# PF.net
KiCad netlist of a schematic drawn in EAGLE
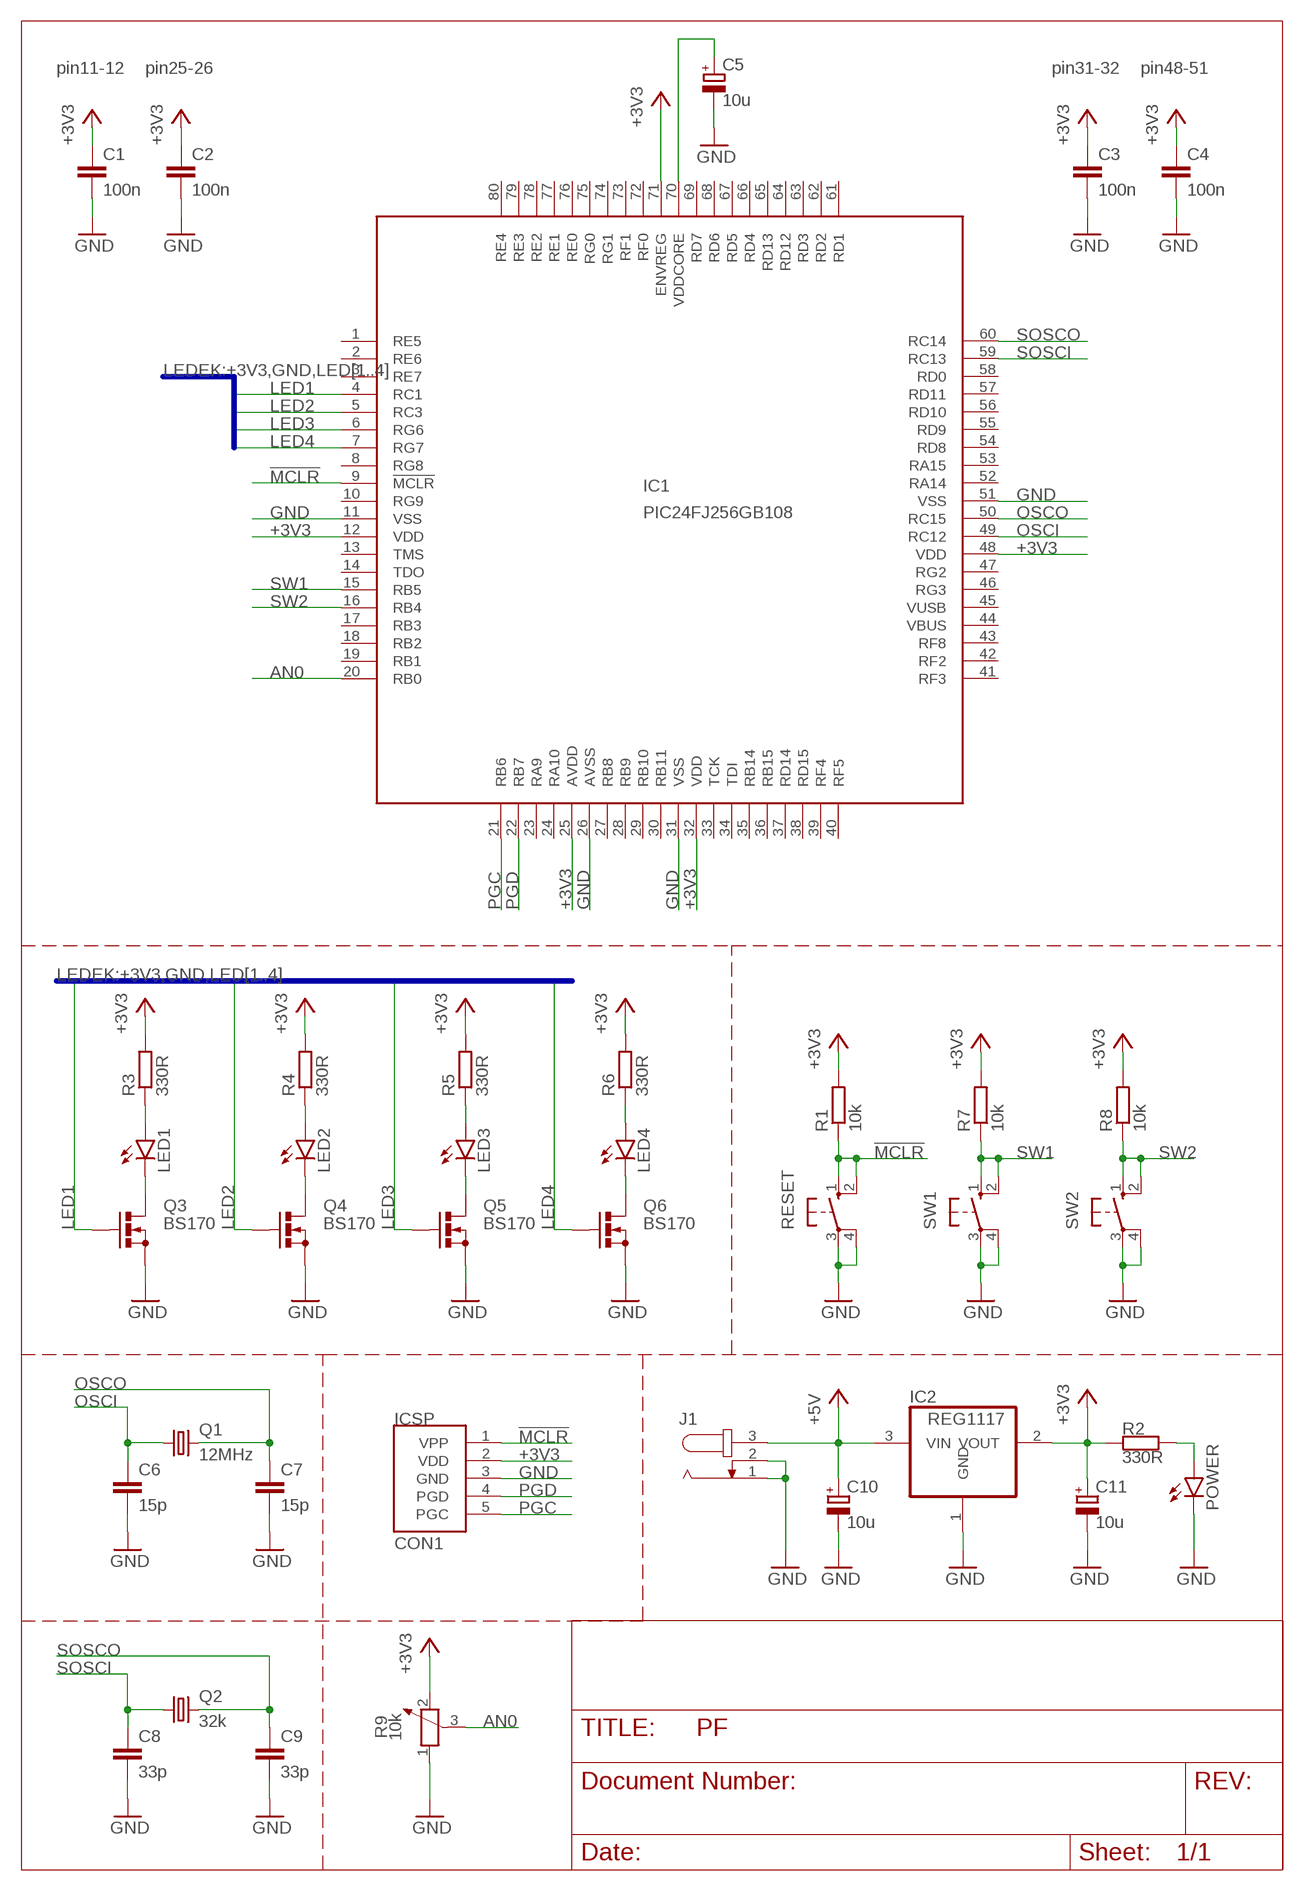
[diagram p0: schematic, sheet 1]

(export (version "E")
  (design (tool "Eeschema 10.0.6"))
  (components
    (comp (ref "C1")
      (value "100n")
      (footprint "eagle-import:C1206")
      (libsource (lib "eagle-import") (part "C-EUC1206"))
    )
    (comp (ref "C2")
      (value "100n")
      (footprint "eagle-import:C1206")
      (libsource (lib "eagle-import") (part "C-EUC1206"))
    )
    (comp (ref "C3")
      (value "100n")
      (footprint "eagle-import:C1206")
      (libsource (lib "eagle-import") (part "C-EUC1206"))
    )
    (comp (ref "C4")
      (value "100n")
      (footprint "eagle-import:C1206")
      (libsource (lib "eagle-import") (part "C-EUC1206"))
    )
    (comp (ref "C5")
      (value "10u")
      (footprint "eagle-import:SMC_D")
      (libsource (lib "eagle-import") (part "CPOL-EUSMCD"))
    )
    (comp (ref "C6")
      (value "15p")
      (footprint "eagle-import:C1206")
      (libsource (lib "eagle-import") (part "C-EUC1206"))
    )
    (comp (ref "C7")
      (value "15p")
      (footprint "eagle-import:C1206")
      (libsource (lib "eagle-import") (part "C-EUC1206"))
    )
    (comp (ref "C8")
      (value "33p")
      (footprint "eagle-import:C1206")
      (libsource (lib "eagle-import") (part "C-EUC1206"))
    )
    (comp (ref "C9")
      (value "33p")
      (footprint "eagle-import:C1206")
      (libsource (lib "eagle-import") (part "C-EUC1206"))
    )
    (comp (ref "C10")
      (value "10u")
      (footprint "eagle-import:SMC_D")
      (libsource (lib "eagle-import") (part "CPOL-EUSMCD"))
    )
    (comp (ref "C11")
      (value "10u")
      (footprint "eagle-import:SMC_D")
      (libsource (lib "eagle-import") (part "CPOL-EUSMCD"))
    )
    (comp (ref "CON1")
      (value "ICSP")
      (footprint "eagle-import:ICSP")
      (libsource (lib "eagle-import") (part "ICSP"))
    )
    (comp (ref "IC1")
      (value "PIC24FJ256GB108")
      (footprint "eagle-import:TQFP80-12X12")
      (fields (field (name "MPN") "PIC24FJ256GB108-I/PT"))
      (libsource (lib "eagle-import") (part "PIC24FJ256GB108"))
    )
    (comp (ref "IC2")
      (value "REG1117")
      (footprint "eagle-import:SOT223")
      (libsource (lib "eagle-import") (part "REG1117"))
    )
    (comp (ref "J1")
      (value "JACK-PLUG0")
      (footprint "eagle-import:SPC4077")
      (libsource (lib "eagle-import") (part "JACK-PLUG0"))
    )
    (comp (ref "LED1")
      (value "LED5MM")
      (footprint "eagle-import:LED5MM")
      (libsource (lib "eagle-import") (part "LED5MM"))
    )
    (comp (ref "LED2")
      (value "LED5MM")
      (footprint "eagle-import:LED5MM")
      (libsource (lib "eagle-import") (part "LED5MM"))
    )
    (comp (ref "LED3")
      (value "LED5MM")
      (footprint "eagle-import:LED5MM")
      (libsource (lib "eagle-import") (part "LED5MM"))
    )
    (comp (ref "LED4")
      (value "LED5MM")
      (footprint "eagle-import:LED5MM")
      (libsource (lib "eagle-import") (part "LED5MM"))
    )
    (comp (ref "POWER")
      (value "LED5MM")
      (footprint "eagle-import:LED5MM")
      (libsource (lib "eagle-import") (part "LED5MM"))
    )
    (comp (ref "Q1")
      (value "12MHz")
      (footprint "eagle-import:HC49U70")
      (libsource (lib "eagle-import") (part "CRYSTALHC49U70"))
    )
    (comp (ref "Q2")
      (value "32k")
      (footprint "eagle-import:TC26H")
      (libsource (lib "eagle-import") (part "CRYSTALTC26H"))
    )
    (comp (ref "Q3")
      (value "BS170")
      (footprint "eagle-import:SOT54E")
      (libsource (lib "eagle-import") (part "BS170"))
    )
    (comp (ref "Q4")
      (value "BS170")
      (footprint "eagle-import:SOT54E")
      (libsource (lib "eagle-import") (part "BS170"))
    )
    (comp (ref "Q5")
      (value "BS170")
      (footprint "eagle-import:SOT54E")
      (libsource (lib "eagle-import") (part "BS170"))
    )
    (comp (ref "Q6")
      (value "BS170")
      (footprint "eagle-import:SOT54E")
      (libsource (lib "eagle-import") (part "BS170"))
    )
    (comp (ref "R1")
      (value "10k")
      (footprint "eagle-import:R1206")
      (libsource (lib "eagle-import") (part "R-EU_R1206"))
    )
    (comp (ref "R2")
      (value "330R")
      (footprint "eagle-import:R1206")
      (libsource (lib "eagle-import") (part "R-EU_R1206"))
    )
    (comp (ref "R3")
      (value "330R")
      (footprint "eagle-import:R1206")
      (libsource (lib "eagle-import") (part "R-EU_R1206"))
    )
    (comp (ref "R4")
      (value "330R")
      (footprint "eagle-import:R1206")
      (libsource (lib "eagle-import") (part "R-EU_R1206"))
    )
    (comp (ref "R5")
      (value "330R")
      (footprint "eagle-import:R1206")
      (libsource (lib "eagle-import") (part "R-EU_R1206"))
    )
    (comp (ref "R6")
      (value "330R")
      (footprint "eagle-import:R1206")
      (libsource (lib "eagle-import") (part "R-EU_R1206"))
    )
    (comp (ref "R7")
      (value "10k")
      (footprint "eagle-import:R1206")
      (libsource (lib "eagle-import") (part "R-EU_R1206"))
    )
    (comp (ref "R8")
      (value "10k")
      (footprint "eagle-import:R1206")
      (libsource (lib "eagle-import") (part "R-EU_R1206"))
    )
    (comp (ref "R9")
      (value "10k")
      (footprint "eagle-import:PT-SPIN")
      (libsource (lib "eagle-import") (part "POTENTIOMETER_PT_SPIN"))
    )
    (comp (ref "RESET")
      (value "10-XX")
      (footprint "eagle-import:B3F-10XX")
      (fields (field (name "MPN") "B3F-1000"))
      (libsource (lib "eagle-import") (part "10-XX"))
    )
    (comp (ref "SW1")
      (value "10-XX")
      (footprint "eagle-import:B3F-10XX")
      (fields (field (name "MPN") "B3F-1000"))
      (libsource (lib "eagle-import") (part "10-XX"))
    )
    (comp (ref "SW2")
      (value "10-XX")
      (footprint "eagle-import:B3F-10XX")
      (fields (field (name "MPN") "B3F-1000"))
      (libsource (lib "eagle-import") (part "10-XX"))
    )
  )
  (nets
    (net (code "5") (name "+3V3") (class "Default")
      (node (ref "C1") (pin "1") (pinfunction "1_1") (pintype "passive"))
      (node (ref "C11") (pin "+") (pinfunction "+_+") (pintype "passive"))
      (node (ref "C2") (pin "1") (pinfunction "1_1") (pintype "passive"))
      (node (ref "C3") (pin "1") (pinfunction "1_1") (pintype "passive"))
      (node (ref "C4") (pin "1") (pinfunction "1_1") (pintype "passive"))
      (node (ref "CON1") (pin "2") (pinfunction "VDD_2") (pintype "bidirectional"))
      (node (ref "IC1") (pin "12") (pinfunction "VDD_12") (pintype "power_in"))
      (node (ref "IC1") (pin "25") (pinfunction "AVDD_25") (pintype "power_in"))
      (node (ref "IC1") (pin "32") (pinfunction "VDD_32") (pintype "power_in"))
      (node (ref "IC1") (pin "48") (pinfunction "VDD_48") (pintype "power_in"))
      (node (ref "IC1") (pin "71") (pinfunction "ENVREG_71") (pintype "passive"))
      (node (ref "IC2") (pin "2") (pinfunction "VOUT_2") (pintype "output"))
      (node (ref "R1") (pin "2") (pinfunction "2_2") (pintype "passive"))
      (node (ref "R2") (pin "2") (pinfunction "2_2") (pintype "passive"))
      (node (ref "R3") (pin "2") (pinfunction "2_2") (pintype "passive"))
      (node (ref "R4") (pin "2") (pinfunction "2_2") (pintype "passive"))
      (node (ref "R5") (pin "2") (pinfunction "2_2") (pintype "passive"))
      (node (ref "R6") (pin "2") (pinfunction "2_2") (pintype "passive"))
      (node (ref "R7") (pin "2") (pinfunction "2_2") (pintype "passive"))
      (node (ref "R8") (pin "2") (pinfunction "2_2") (pintype "passive"))
      (node (ref "R9") (pin "2") (pinfunction "2_2") (pintype "passive"))
    )
    (net (code "6") (name "+5V") (class "Default")
      (node (ref "C10") (pin "+") (pinfunction "+_+") (pintype "passive"))
      (node (ref "IC2") (pin "3") (pinfunction "VIN_3") (pintype "input"))
      (node (ref "J1") (pin "3") (pinfunction "3_3") (pintype "passive"))
    )
    (net (code "7") (name "/AN0") (class "Default")
      (node (ref "IC1") (pin "20") (pinfunction "RB0_20") (pintype "bidirectional"))
      (node (ref "R9") (pin "3") (pinfunction "3_3") (pintype "passive"))
    )
    (net (code "8") (name "/LED1") (class "Default")
      (node (ref "IC1") (pin "4") (pinfunction "RC1_4") (pintype "bidirectional"))
      (node (ref "Q3") (pin "G") (pinfunction "G_G") (pintype "passive"))
    )
    (net (code "9") (name "/LED2") (class "Default")
      (node (ref "IC1") (pin "5") (pinfunction "RC3_5") (pintype "bidirectional"))
      (node (ref "Q4") (pin "G") (pinfunction "G_G") (pintype "passive"))
    )
    (net (code "10") (name "/LED3") (class "Default")
      (node (ref "IC1") (pin "6") (pinfunction "RG6_6") (pintype "bidirectional"))
      (node (ref "Q5") (pin "G") (pinfunction "G_G") (pintype "passive"))
    )
    (net (code "11") (name "/LED4") (class "Default")
      (node (ref "IC1") (pin "7") (pinfunction "RG7_7") (pintype "bidirectional"))
      (node (ref "Q6") (pin "G") (pinfunction "G_G") (pintype "passive"))
    )
    (net (code "13") (name "/OSCI") (class "Default")
      (node (ref "C6") (pin "1") (pinfunction "1_1") (pintype "passive"))
      (node (ref "IC1") (pin "49") (pinfunction "RC12_49") (pintype "bidirectional"))
      (node (ref "Q1") (pin "1") (pinfunction "1_1") (pintype "passive"))
    )
    (net (code "14") (name "/OSCO") (class "Default")
      (node (ref "C7") (pin "1") (pinfunction "1_1") (pintype "passive"))
      (node (ref "IC1") (pin "50") (pinfunction "RC15_50") (pintype "bidirectional"))
      (node (ref "Q1") (pin "2") (pinfunction "2_2") (pintype "passive"))
    )
    (net (code "15") (name "/PGC") (class "Default")
      (node (ref "CON1") (pin "5") (pinfunction "PGC_5") (pintype "bidirectional"))
      (node (ref "IC1") (pin "21") (pinfunction "RB6_21") (pintype "bidirectional"))
    )
    (net (code "16") (name "/PGD") (class "Default")
      (node (ref "CON1") (pin "4") (pinfunction "PGD_4") (pintype "bidirectional"))
      (node (ref "IC1") (pin "22") (pinfunction "RB7_22") (pintype "bidirectional"))
    )
    (net (code "17") (name "/SOSCI") (class "Default")
      (node (ref "C8") (pin "1") (pinfunction "1_1") (pintype "passive"))
      (node (ref "IC1") (pin "59") (pinfunction "RC13_59") (pintype "bidirectional"))
      (node (ref "Q2") (pin "1") (pinfunction "1_1") (pintype "passive"))
    )
    (net (code "18") (name "/SOSCO") (class "Default")
      (node (ref "C9") (pin "1") (pinfunction "1_1") (pintype "passive"))
      (node (ref "IC1") (pin "60") (pinfunction "RC14_60") (pintype "bidirectional"))
      (node (ref "Q2") (pin "2") (pinfunction "2_2") (pintype "passive"))
    )
    (net (code "19") (name "/SW1") (class "Default")
      (node (ref "IC1") (pin "15") (pinfunction "RB5_15") (pintype "bidirectional"))
      (node (ref "R7") (pin "1") (pinfunction "1_1") (pintype "passive"))
      (node (ref "SW1") (pin "1") (pinfunction "S_1") (pintype "passive"))
      (node (ref "SW1") (pin "2") (pinfunction "S1_2") (pintype "passive"))
    )
    (net (code "20") (name "/SW2") (class "Default")
      (node (ref "IC1") (pin "16") (pinfunction "RB4_16") (pintype "bidirectional"))
      (node (ref "R8") (pin "1") (pinfunction "1_1") (pintype "passive"))
      (node (ref "SW2") (pin "1") (pinfunction "S_1") (pintype "passive"))
      (node (ref "SW2") (pin "2") (pinfunction "S1_2") (pintype "passive"))
    )
    (net (code "21") (name "/~{MCLR}") (class "Default")
      (node (ref "CON1") (pin "1") (pinfunction "VPP_1") (pintype "bidirectional"))
      (node (ref "IC1") (pin "9") (pinfunction "~{MCLR}_9") (pintype "bidirectional"))
      (node (ref "R1") (pin "1") (pinfunction "1_1") (pintype "passive"))
      (node (ref "RESET") (pin "1") (pinfunction "S_1") (pintype "passive"))
      (node (ref "RESET") (pin "2") (pinfunction "S1_2") (pintype "passive"))
    )
    (net (code "22") (name "GND") (class "Default")
      (node (ref "C1") (pin "2") (pinfunction "2_2") (pintype "passive"))
      (node (ref "C10") (pin "-") (pinfunction "-_-") (pintype "passive"))
      (node (ref "C11") (pin "-") (pinfunction "-_-") (pintype "passive"))
      (node (ref "C2") (pin "2") (pinfunction "2_2") (pintype "passive"))
      (node (ref "C3") (pin "2") (pinfunction "2_2") (pintype "passive"))
      (node (ref "C4") (pin "2") (pinfunction "2_2") (pintype "passive"))
      (node (ref "C5") (pin "-") (pinfunction "-_-") (pintype "passive"))
      (node (ref "C6") (pin "2") (pinfunction "2_2") (pintype "passive"))
      (node (ref "C7") (pin "2") (pinfunction "2_2") (pintype "passive"))
      (node (ref "C8") (pin "2") (pinfunction "2_2") (pintype "passive"))
      (node (ref "C9") (pin "2") (pinfunction "2_2") (pintype "passive"))
      (node (ref "CON1") (pin "3") (pinfunction "GND_3") (pintype "bidirectional"))
      (node (ref "IC1") (pin "11") (pinfunction "VSS_11") (pintype "power_in"))
      (node (ref "IC1") (pin "26") (pinfunction "AVSS_26") (pintype "power_in"))
      (node (ref "IC1") (pin "31") (pinfunction "VSS_31") (pintype "power_in"))
      (node (ref "IC1") (pin "51") (pinfunction "VSS_51") (pintype "power_in"))
      (node (ref "IC2") (pin "1") (pinfunction "GND_1") (pintype "power_in"))
      (node (ref "J1") (pin "1") (pinfunction "1_1") (pintype "passive"))
      (node (ref "J1") (pin "2") (pinfunction "2_2") (pintype "passive"))
      (node (ref "POWER") (pin "K") (pinfunction "C_K") (pintype "passive"))
      (node (ref "Q3") (pin "S") (pinfunction "S_S") (pintype "passive"))
      (node (ref "Q4") (pin "S") (pinfunction "S_S") (pintype "passive"))
      (node (ref "Q5") (pin "S") (pinfunction "S_S") (pintype "passive"))
      (node (ref "Q6") (pin "S") (pinfunction "S_S") (pintype "passive"))
      (node (ref "R9") (pin "1") (pinfunction "1_1") (pintype "passive"))
      (node (ref "RESET") (pin "3") (pinfunction "P_3") (pintype "passive"))
      (node (ref "RESET") (pin "4") (pinfunction "P1_4") (pintype "passive"))
      (node (ref "SW1") (pin "3") (pinfunction "P_3") (pintype "passive"))
      (node (ref "SW1") (pin "4") (pinfunction "P1_4") (pintype "passive"))
      (node (ref "SW2") (pin "3") (pinfunction "P_3") (pintype "passive"))
      (node (ref "SW2") (pin "4") (pinfunction "P1_4") (pintype "passive"))
    )
    (net (code "23") (name "Net-(IC1-VDDCORE)") (class "Default")
      (node (ref "C5") (pin "+") (pinfunction "+_+") (pintype "passive"))
      (node (ref "IC1") (pin "70") (pinfunction "VDDCORE_70") (pintype "power_in"))
    )
    (net (code "24") (name "Net-(LED1-C)") (class "Default")
      (node (ref "LED1") (pin "K") (pinfunction "C_K") (pintype "passive"))
      (node (ref "Q3") (pin "D") (pinfunction "D_D") (pintype "passive"))
    )
    (net (code "25") (name "Net-(LED1-PadA)") (class "Default")
      (node (ref "LED1") (pin "A") (pinfunction "A_A") (pintype "passive"))
      (node (ref "R3") (pin "1") (pinfunction "1_1") (pintype "passive"))
    )
    (net (code "26") (name "Net-(LED2-C)") (class "Default")
      (node (ref "LED2") (pin "K") (pinfunction "C_K") (pintype "passive"))
      (node (ref "Q4") (pin "D") (pinfunction "D_D") (pintype "passive"))
    )
    (net (code "27") (name "Net-(LED2-PadA)") (class "Default")
      (node (ref "LED2") (pin "A") (pinfunction "A_A") (pintype "passive"))
      (node (ref "R4") (pin "1") (pinfunction "1_1") (pintype "passive"))
    )
    (net (code "28") (name "Net-(LED3-C)") (class "Default")
      (node (ref "LED3") (pin "K") (pinfunction "C_K") (pintype "passive"))
      (node (ref "Q5") (pin "D") (pinfunction "D_D") (pintype "passive"))
    )
    (net (code "29") (name "Net-(LED3-PadA)") (class "Default")
      (node (ref "LED3") (pin "A") (pinfunction "A_A") (pintype "passive"))
      (node (ref "R5") (pin "1") (pinfunction "1_1") (pintype "passive"))
    )
    (net (code "30") (name "Net-(LED4-C)") (class "Default")
      (node (ref "LED4") (pin "K") (pinfunction "C_K") (pintype "passive"))
      (node (ref "Q6") (pin "D") (pinfunction "D_D") (pintype "passive"))
    )
    (net (code "31") (name "Net-(LED4-PadA)") (class "Default")
      (node (ref "LED4") (pin "A") (pinfunction "A_A") (pintype "passive"))
      (node (ref "R6") (pin "1") (pinfunction "1_1") (pintype "passive"))
    )
    (net (code "32") (name "Net-(POWER-PadA)") (class "Default")
      (node (ref "POWER") (pin "A") (pinfunction "A_A") (pintype "passive"))
      (node (ref "R2") (pin "1") (pinfunction "1_1") (pintype "passive"))
    )
    (net (code "33") (name "unconnected-(IC1-RA9-Pad23)") (class "Default")
      (node (ref "IC1") (pin "23") (pinfunction "RA9_23") (pintype "bidirectional"))
    )
    (net (code "34") (name "unconnected-(IC1-RA10-Pad24)") (class "Default")
      (node (ref "IC1") (pin "24") (pinfunction "RA10_24") (pintype "bidirectional"))
    )
    (net (code "35") (name "unconnected-(IC1-RA14-Pad52)") (class "Default")
      (node (ref "IC1") (pin "52") (pinfunction "RA14_52") (pintype "bidirectional"))
    )
    (net (code "36") (name "unconnected-(IC1-RA15-Pad53)") (class "Default")
      (node (ref "IC1") (pin "53") (pinfunction "RA15_53") (pintype "bidirectional"))
    )
    (net (code "37") (name "unconnected-(IC1-RB1-Pad19)") (class "Default")
      (node (ref "IC1") (pin "19") (pinfunction "RB1_19") (pintype "bidirectional"))
    )
    (net (code "38") (name "unconnected-(IC1-RB2-Pad18)") (class "Default")
      (node (ref "IC1") (pin "18") (pinfunction "RB2_18") (pintype "bidirectional"))
    )
    (net (code "39") (name "unconnected-(IC1-RB3-Pad17)") (class "Default")
      (node (ref "IC1") (pin "17") (pinfunction "RB3_17") (pintype "bidirectional"))
    )
    (net (code "40") (name "unconnected-(IC1-RB8-Pad27)") (class "Default")
      (node (ref "IC1") (pin "27") (pinfunction "RB8_27") (pintype "bidirectional"))
    )
    (net (code "41") (name "unconnected-(IC1-RB9-Pad28)") (class "Default")
      (node (ref "IC1") (pin "28") (pinfunction "RB9_28") (pintype "bidirectional"))
    )
    (net (code "42") (name "unconnected-(IC1-RB10-Pad29)") (class "Default")
      (node (ref "IC1") (pin "29") (pinfunction "RB10_29") (pintype "bidirectional"))
    )
    (net (code "43") (name "unconnected-(IC1-RB11-Pad30)") (class "Default")
      (node (ref "IC1") (pin "30") (pinfunction "RB11_30") (pintype "bidirectional"))
    )
    (net (code "44") (name "unconnected-(IC1-RB14-Pad35)") (class "Default")
      (node (ref "IC1") (pin "35") (pinfunction "RB14_35") (pintype "bidirectional"))
    )
    (net (code "45") (name "unconnected-(IC1-RB15-Pad36)") (class "Default")
      (node (ref "IC1") (pin "36") (pinfunction "RB15_36") (pintype "bidirectional"))
    )
    (net (code "46") (name "unconnected-(IC1-RD0-Pad58)") (class "Default")
      (node (ref "IC1") (pin "58") (pinfunction "RD0_58") (pintype "bidirectional"))
    )
    (net (code "47") (name "unconnected-(IC1-RD1-Pad61)") (class "Default")
      (node (ref "IC1") (pin "61") (pinfunction "RD1_61") (pintype "bidirectional"))
    )
    (net (code "48") (name "unconnected-(IC1-RD2-Pad62)") (class "Default")
      (node (ref "IC1") (pin "62") (pinfunction "RD2_62") (pintype "bidirectional"))
    )
    (net (code "49") (name "unconnected-(IC1-RD3-Pad63)") (class "Default")
      (node (ref "IC1") (pin "63") (pinfunction "RD3_63") (pintype "bidirectional"))
    )
    (net (code "50") (name "unconnected-(IC1-RD4-Pad66)") (class "Default")
      (node (ref "IC1") (pin "66") (pinfunction "RD4_66") (pintype "bidirectional"))
    )
    (net (code "51") (name "unconnected-(IC1-RD5-Pad67)") (class "Default")
      (node (ref "IC1") (pin "67") (pinfunction "RD5_67") (pintype "bidirectional"))
    )
    (net (code "52") (name "unconnected-(IC1-RD6-Pad68)") (class "Default")
      (node (ref "IC1") (pin "68") (pinfunction "RD6_68") (pintype "bidirectional"))
    )
    (net (code "53") (name "unconnected-(IC1-RD7-Pad69)") (class "Default")
      (node (ref "IC1") (pin "69") (pinfunction "RD7_69") (pintype "bidirectional"))
    )
    (net (code "54") (name "unconnected-(IC1-RD8-Pad54)") (class "Default")
      (node (ref "IC1") (pin "54") (pinfunction "RD8_54") (pintype "bidirectional"))
    )
    (net (code "55") (name "unconnected-(IC1-RD9-Pad55)") (class "Default")
      (node (ref "IC1") (pin "55") (pinfunction "RD9_55") (pintype "bidirectional"))
    )
    (net (code "56") (name "unconnected-(IC1-RD10-Pad56)") (class "Default")
      (node (ref "IC1") (pin "56") (pinfunction "RD10_56") (pintype "bidirectional"))
    )
    (net (code "57") (name "unconnected-(IC1-RD11-Pad57)") (class "Default")
      (node (ref "IC1") (pin "57") (pinfunction "RD11_57") (pintype "bidirectional"))
    )
    (net (code "58") (name "unconnected-(IC1-RD12-Pad64)") (class "Default")
      (node (ref "IC1") (pin "64") (pinfunction "RD12_64") (pintype "bidirectional"))
    )
    (net (code "59") (name "unconnected-(IC1-RD13-Pad65)") (class "Default")
      (node (ref "IC1") (pin "65") (pinfunction "RD13_65") (pintype "bidirectional"))
    )
    (net (code "60") (name "unconnected-(IC1-RD14-Pad37)") (class "Default")
      (node (ref "IC1") (pin "37") (pinfunction "RD14_37") (pintype "bidirectional"))
    )
    (net (code "61") (name "unconnected-(IC1-RD15-Pad38)") (class "Default")
      (node (ref "IC1") (pin "38") (pinfunction "RD15_38") (pintype "bidirectional"))
    )
    (net (code "62") (name "unconnected-(IC1-RE0-Pad76)") (class "Default")
      (node (ref "IC1") (pin "76") (pinfunction "RE0_76") (pintype "bidirectional"))
    )
    (net (code "63") (name "unconnected-(IC1-RE1-Pad77)") (class "Default")
      (node (ref "IC1") (pin "77") (pinfunction "RE1_77") (pintype "bidirectional"))
    )
    (net (code "64") (name "unconnected-(IC1-RE2-Pad78)") (class "Default")
      (node (ref "IC1") (pin "78") (pinfunction "RE2_78") (pintype "bidirectional"))
    )
    (net (code "65") (name "unconnected-(IC1-RE3-Pad79)") (class "Default")
      (node (ref "IC1") (pin "79") (pinfunction "RE3_79") (pintype "bidirectional"))
    )
    (net (code "66") (name "unconnected-(IC1-RE4-Pad80)") (class "Default")
      (node (ref "IC1") (pin "80") (pinfunction "RE4_80") (pintype "bidirectional"))
    )
    (net (code "67") (name "unconnected-(IC1-RE5-Pad1)") (class "Default")
      (node (ref "IC1") (pin "1") (pinfunction "RE5_1") (pintype "bidirectional"))
    )
    (net (code "68") (name "unconnected-(IC1-RE6-Pad2)") (class "Default")
      (node (ref "IC1") (pin "2") (pinfunction "RE6_2") (pintype "bidirectional"))
    )
    (net (code "69") (name "unconnected-(IC1-RE7-Pad3)") (class "Default")
      (node (ref "IC1") (pin "3") (pinfunction "RE7_3") (pintype "bidirectional"))
    )
    (net (code "70") (name "unconnected-(IC1-RF0-Pad72)") (class "Default")
      (node (ref "IC1") (pin "72") (pinfunction "RF0_72") (pintype "bidirectional"))
    )
    (net (code "71") (name "unconnected-(IC1-RF1-Pad73)") (class "Default")
      (node (ref "IC1") (pin "73") (pinfunction "RF1_73") (pintype "bidirectional"))
    )
    (net (code "72") (name "unconnected-(IC1-RF2-Pad42)") (class "Default")
      (node (ref "IC1") (pin "42") (pinfunction "RF2_42") (pintype "bidirectional"))
    )
    (net (code "73") (name "unconnected-(IC1-RF3-Pad41)") (class "Default")
      (node (ref "IC1") (pin "41") (pinfunction "RF3_41") (pintype "bidirectional"))
    )
    (net (code "74") (name "unconnected-(IC1-RF4-Pad39)") (class "Default")
      (node (ref "IC1") (pin "39") (pinfunction "RF4_39") (pintype "bidirectional"))
    )
    (net (code "75") (name "unconnected-(IC1-RF5-Pad40)") (class "Default")
      (node (ref "IC1") (pin "40") (pinfunction "RF5_40") (pintype "bidirectional"))
    )
    (net (code "76") (name "unconnected-(IC1-RF8-Pad43)") (class "Default")
      (node (ref "IC1") (pin "43") (pinfunction "RF8_43") (pintype "bidirectional"))
    )
    (net (code "77") (name "unconnected-(IC1-RG0-Pad75)") (class "Default")
      (node (ref "IC1") (pin "75") (pinfunction "RG0_75") (pintype "bidirectional"))
    )
    (net (code "78") (name "unconnected-(IC1-RG1-Pad74)") (class "Default")
      (node (ref "IC1") (pin "74") (pinfunction "RG1_74") (pintype "bidirectional"))
    )
    (net (code "79") (name "unconnected-(IC1-RG2-Pad47)") (class "Default")
      (node (ref "IC1") (pin "47") (pinfunction "RG2_47") (pintype "bidirectional"))
    )
    (net (code "80") (name "unconnected-(IC1-RG3-Pad46)") (class "Default")
      (node (ref "IC1") (pin "46") (pinfunction "RG3_46") (pintype "bidirectional"))
    )
    (net (code "81") (name "unconnected-(IC1-RG8-Pad8)") (class "Default")
      (node (ref "IC1") (pin "8") (pinfunction "RG8_8") (pintype "bidirectional"))
    )
    (net (code "82") (name "unconnected-(IC1-RG9-Pad10)") (class "Default")
      (node (ref "IC1") (pin "10") (pinfunction "RG9_10") (pintype "bidirectional"))
    )
    (net (code "83") (name "unconnected-(IC1-TCK-Pad33)") (class "Default")
      (node (ref "IC1") (pin "33") (pinfunction "TCK_33") (pintype "input"))
    )
    (net (code "84") (name "unconnected-(IC1-TDI-Pad34)") (class "Default")
      (node (ref "IC1") (pin "34") (pinfunction "TDI_34") (pintype "input"))
    )
    (net (code "85") (name "unconnected-(IC1-TDO-Pad14)") (class "Default")
      (node (ref "IC1") (pin "14") (pinfunction "TDO_14") (pintype "output"))
    )
    (net (code "86") (name "unconnected-(IC1-TMS-Pad13)") (class "Default")
      (node (ref "IC1") (pin "13") (pinfunction "TMS_13") (pintype "input"))
    )
    (net (code "87") (name "unconnected-(IC1-VBUS-Pad44)") (class "Default")
      (node (ref "IC1") (pin "44") (pinfunction "VBUS_44") (pintype "passive"))
    )
    (net (code "88") (name "unconnected-(IC1-VUSB-Pad45)") (class "Default")
      (node (ref "IC1") (pin "45") (pinfunction "VUSB_45") (pintype "passive"))
    )
  )
)
